# byle_cake.net
KiCad netlist of a schematic drawn in EAGLE
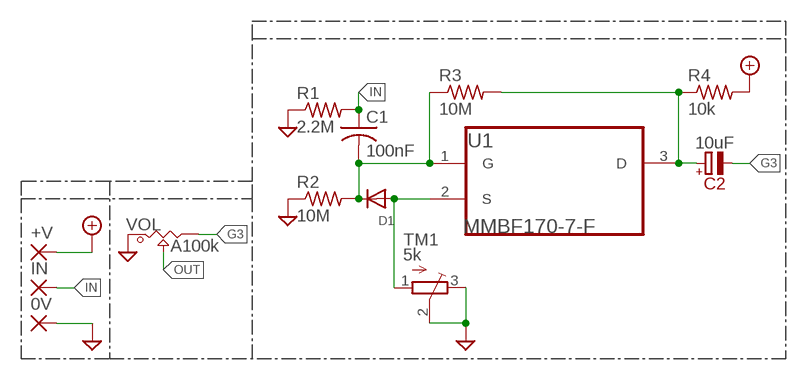
[diagram p0: schematic, sheet 1]

(export (version "E")
  (design (tool "Eeschema 10.0.6"))
  (components
    (comp (ref "+V")
      (value "SMD2")
      (footprint "eagle-import:SMD1,27-2,54")
      (libsource (lib "eagle-import") (part "SMD2"))
    )
    (comp (ref "0V")
      (value "SMD2")
      (footprint "eagle-import:SMD1,27-2,54")
      (libsource (lib "eagle-import") (part "SMD2"))
    )
    (comp (ref "C1")
      (value "100nF")
      (footprint "eagle-import:C0603")
      (libsource (lib "eagle-import") (part "C-USC0603"))
    )
    (comp (ref "C2")
      (value "10uF")
      (footprint "eagle-import:PAN_B")
      (libsource (lib "eagle-import") (part "PAN_B"))
    )
    (comp (ref "D1")
      (value "DIODESOD-123")
      (footprint "eagle-import:SOD-123")
      (libsource (lib "eagle-import") (part "DIODESOD-123"))
    )
    (comp (ref "IN")
      (value "SMD2")
      (footprint "eagle-import:SMD1,27-2,54")
      (libsource (lib "eagle-import") (part "SMD2"))
    )
    (comp (ref "R1")
      (value "2.2M")
      (footprint "eagle-import:R0603")
      (libsource (lib "eagle-import") (part "R-US_R0603"))
    )
    (comp (ref "R2")
      (value "10M")
      (footprint "eagle-import:R0603")
      (libsource (lib "eagle-import") (part "R-US_R0603"))
    )
    (comp (ref "R3")
      (value "10M")
      (footprint "eagle-import:R0603")
      (libsource (lib "eagle-import") (part "R-US_R0603"))
    )
    (comp (ref "R4")
      (value "10k")
      (footprint "eagle-import:R0603")
      (libsource (lib "eagle-import") (part "R-US_R0603"))
    )
    (comp (ref "TM1")
      (value "5k")
      (footprint "eagle-import:TC33X")
      (libsource (lib "eagle-import") (part "TRIMPOTTC33X"))
    )
    (comp (ref "U1")
      (value "MMBF170-7-F")
      (footprint "eagle-import:SOT103P240X110-3N")
      (fields (field (name "MF") "Diodes Inc."))
      (libsource (lib "eagle-import") (part "MMBF170-7-F"))
    )
    (comp (ref "VOL")
      (value "A100k")
      (footprint "eagle-import:POT_9MM_SMD")
      (libsource (lib "eagle-import") (part "POT_9MM_SMD"))
    )
  )
  (nets
    (net (code "1") (name "+9V") (class "Default")
      (node (ref "+V") (pin "1") (pinfunction "P_1") (pintype "passive"))
      (node (ref "R4") (pin "2") (pinfunction "2_2") (pintype "passive"))
    )
    (net (code "2") (name "G3") (class "Default")
      (node (ref "C2") (pin "2-") (pinfunction "-_2-") (pintype "passive"))
      (node (ref "VOL") (pin "3") (pinfunction "3_3") (pintype "bidirectional"))
    )
    (net (code "3") (name "GND") (class "Default")
      (node (ref "0V") (pin "1") (pinfunction "P_1") (pintype "passive"))
      (node (ref "R1") (pin "1") (pinfunction "1_1") (pintype "passive"))
      (node (ref "R2") (pin "1") (pinfunction "1_1") (pintype "passive"))
      (node (ref "TM1") (pin "2") (pinfunction "S_2") (pintype "passive"))
      (node (ref "TM1") (pin "3") (pinfunction "E_3") (pintype "passive"))
      (node (ref "VOL") (pin "1") (pinfunction "1_1") (pintype "bidirectional"))
    )
    (net (code "4") (name "IN") (class "Default")
      (node (ref "C1") (pin "1") (pinfunction "1_1") (pintype "passive"))
      (node (ref "IN") (pin "1") (pinfunction "P_1") (pintype "passive"))
      (node (ref "R1") (pin "2") (pinfunction "2_2") (pintype "passive"))
    )
    (net (code "5") (name "Net-(C2-+)") (class "Default")
      (node (ref "C2") (pin "1+") (pinfunction "+_1+") (pintype "passive"))
      (node (ref "R3") (pin "2") (pinfunction "2_2") (pintype "passive"))
      (node (ref "R4") (pin "1") (pinfunction "1_1") (pintype "passive"))
      (node (ref "U1") (pin "3") (pinfunction "D_3") (pintype "output"))
    )
    (net (code "6") (name "Net-(TM1-A)") (class "Default")
      (node (ref "D1") (pin "A") (pinfunction "A_A") (pintype "passive"))
      (node (ref "TM1") (pin "1") (pinfunction "A_1") (pintype "passive"))
      (node (ref "U1") (pin "2") (pinfunction "S_2") (pintype "passive"))
    )
    (net (code "7") (name "Net-(U1-G)") (class "Default")
      (node (ref "C1") (pin "2") (pinfunction "2_2") (pintype "passive"))
      (node (ref "D1") (pin "C") (pinfunction "C_C") (pintype "passive"))
      (node (ref "R2") (pin "2") (pinfunction "2_2") (pintype "passive"))
      (node (ref "R3") (pin "1") (pinfunction "1_1") (pintype "passive"))
      (node (ref "U1") (pin "1") (pinfunction "G_1") (pintype "input"))
    )
    (net (code "8") (name "OUT") (class "Default")
      (node (ref "VOL") (pin "2") (pinfunction "2_2") (pintype "bidirectional"))
    )
  )
)
